# WhiteNoise.net
KiCad netlist of a schematic drawn in EasyEDA
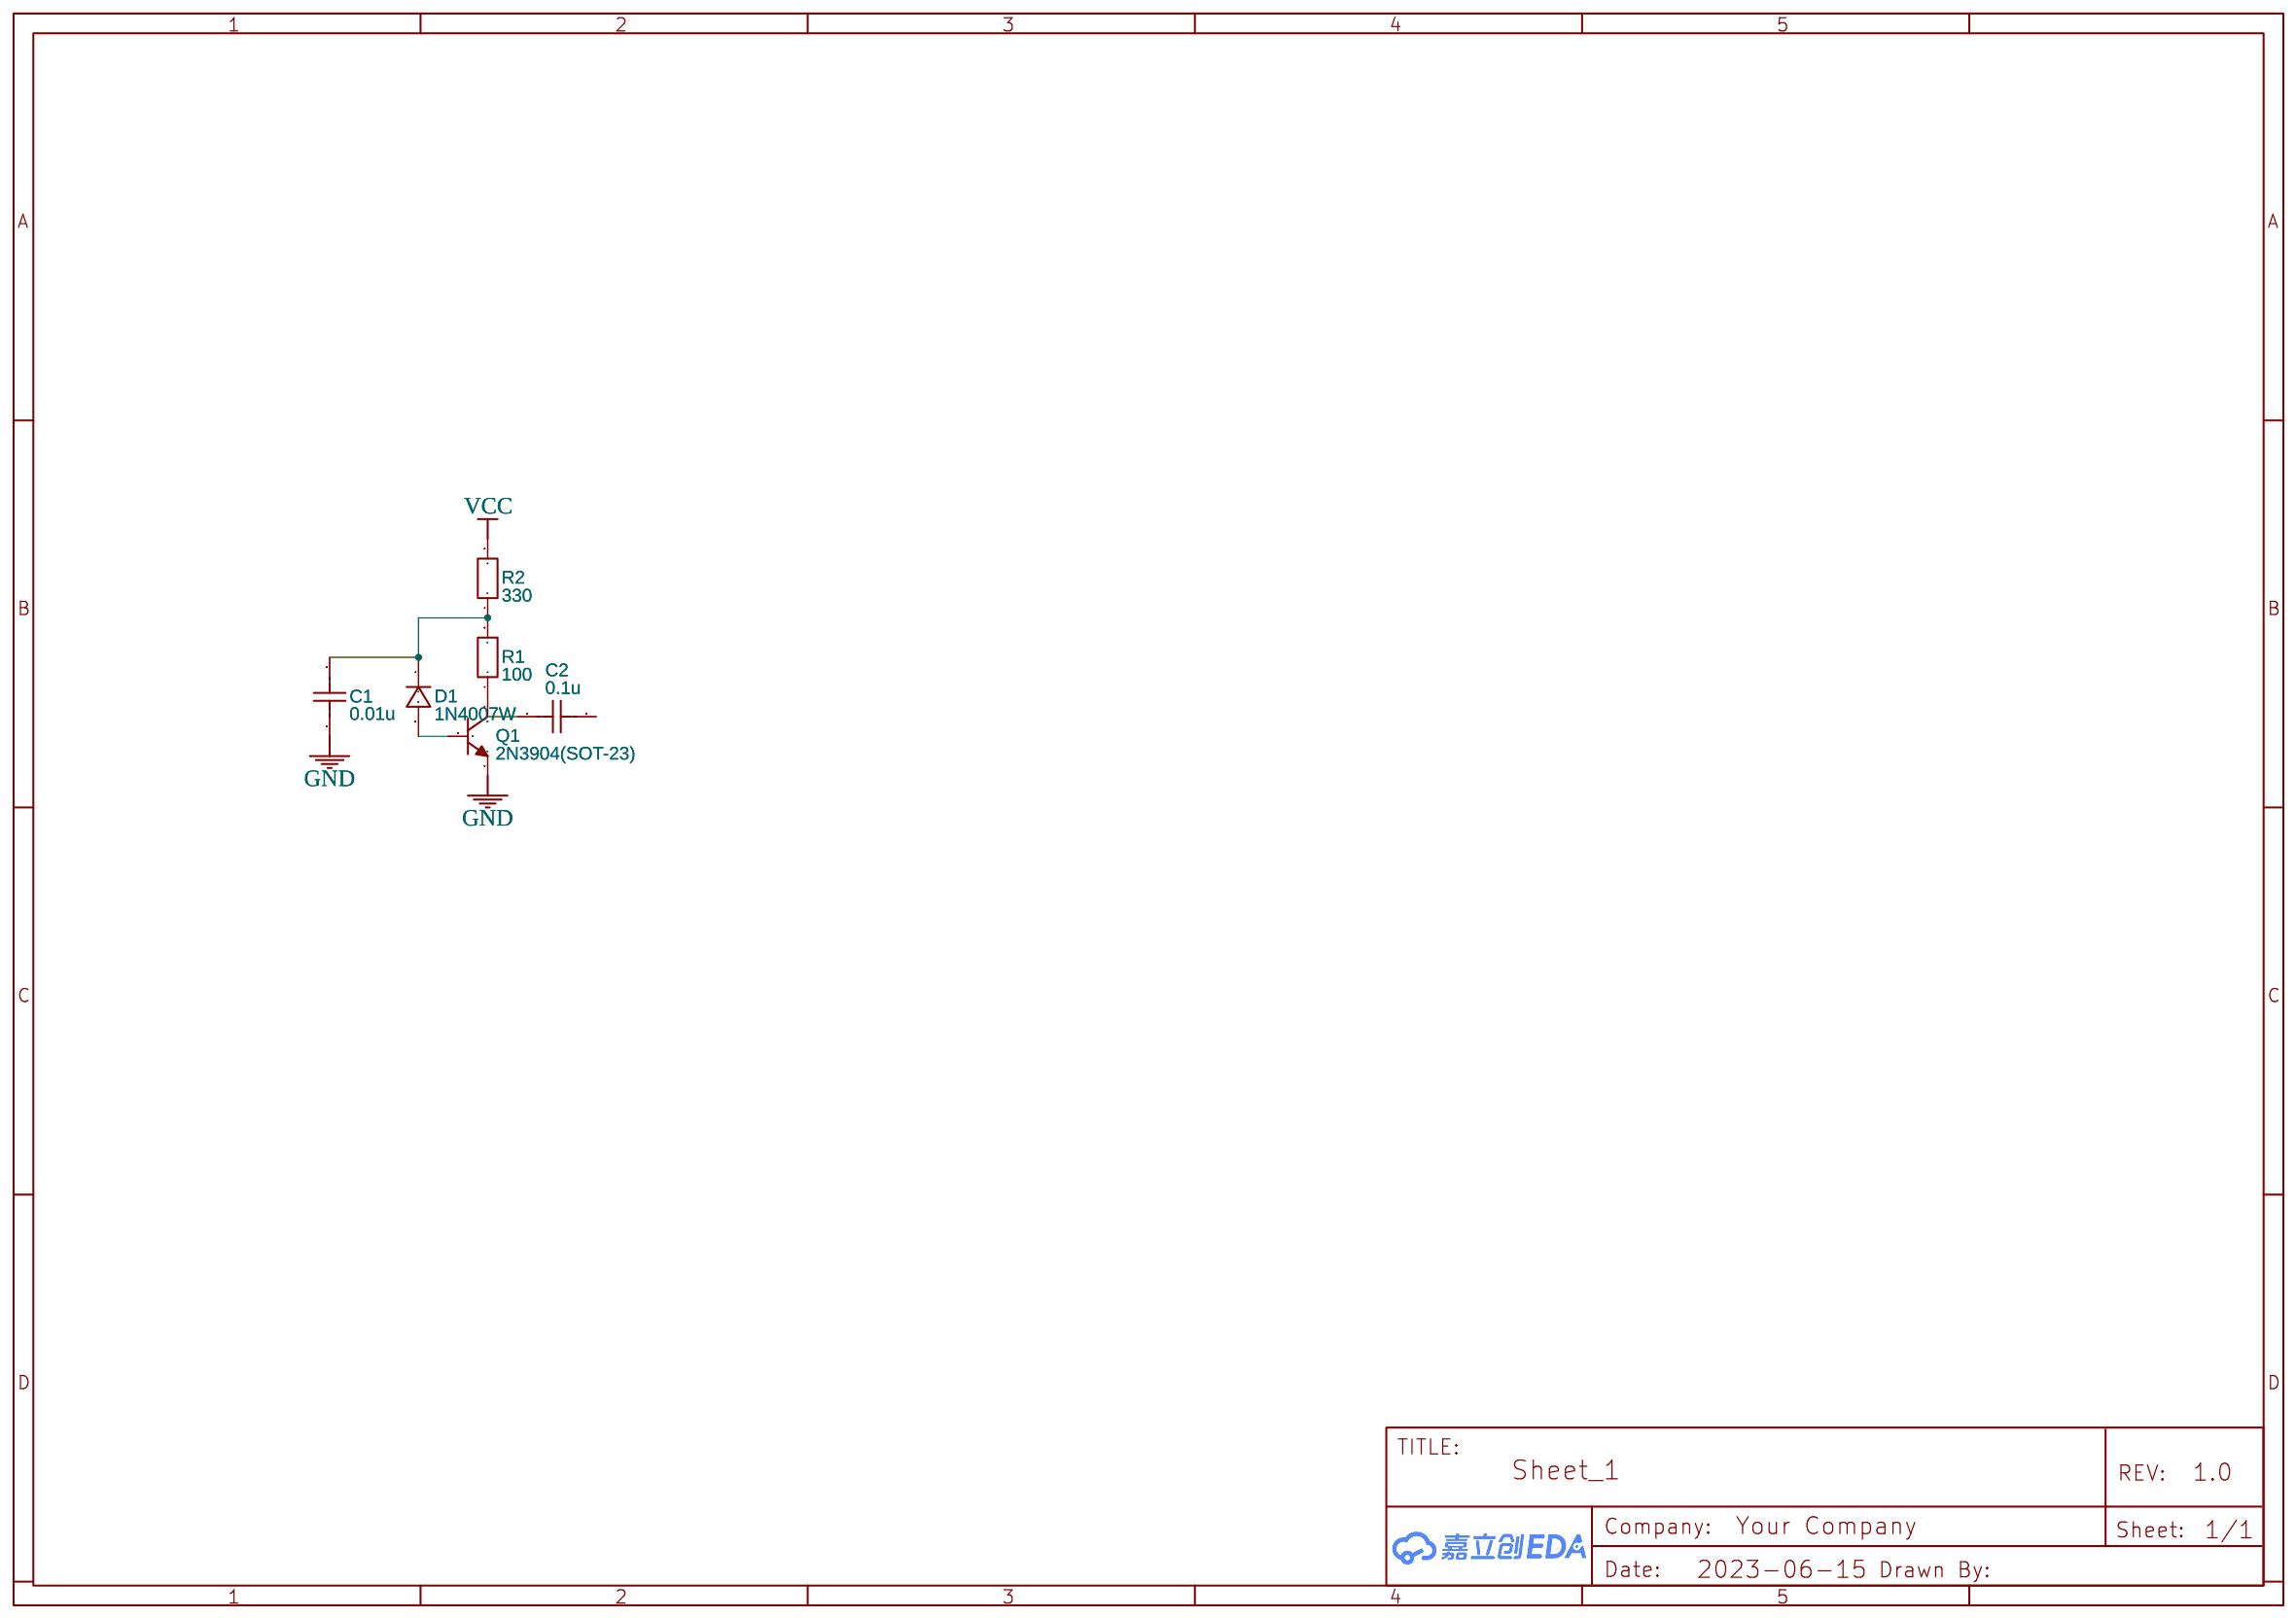
[diagram p0: schematic sheet]

(export (version "E")
  (design (tool "Eeschema 10.0.6"))
  (components
    (comp (ref "C1") (value "0.01u") (libsource (lib "") (part "C_0603_US")))
    (comp (ref "C2") (value "0.1u") (libsource (lib "") (part "C_0603_US_1")))
    (comp (ref "D1")
      (value "1N4007W")
      (fields (field (name "BOM_Supplier Part") "C328592"))
      (libsource (lib "") (part "1N4007W"))
    )
    (comp (ref "Q1")
      (value "2N3904(SOT-23)")
      (fields
        (field (name "BOM_Manufacturer Part") "2n3904S-RTK/PS")
        (field (name "BOM_Supplier Part") "C18536")
      )
      (libsource (lib "") (part "2N3904(SOT-23)"))
    )
    (comp (ref "R1") (value "100") (libsource (lib "") (part "R_0603_EU")))
    (comp (ref "R2") (value "330") (libsource (lib "") (part "R_0603_EU")))
  )
  (nets
    (net (code "1") (name "GND") (class "Default")
      (node (ref "C1") (pin "1") (pinfunction "1_1") (pintype "unspecified"))
      (node (ref "Q1") (pin "2") (pinfunction "E_2") (pintype "input"))
    )
    (net (code "2") (name "Net-(C1-Pad2)") (class "Default")
      (node (ref "C1") (pin "2") (pinfunction "2_2") (pintype "unspecified"))
      (node (ref "D1") (pin "1") (pinfunction "1_1") (pintype "unspecified"))
      (node (ref "R1") (pin "2") (pinfunction "2_2") (pintype "unspecified"))
      (node (ref "R2") (pin "1") (pinfunction "1_1") (pintype "unspecified"))
    )
    (net (code "3") (name "Net-(Q1-B)") (class "Default")
      (node (ref "D1") (pin "2") (pinfunction "2_2") (pintype "unspecified"))
      (node (ref "Q1") (pin "3") (pinfunction "B_3") (pintype "input"))
    )
    (net (code "4") (name "Net-(Q1-C)") (class "Default")
      (node (ref "Q1") (pin "1") (pinfunction "C_1") (pintype "input"))
      (node (ref "R1") (pin "1") (pinfunction "1_1") (pintype "unspecified"))
    )
    (net (code "5") (name "VCC") (class "Default")
      (node (ref "R2") (pin "2") (pinfunction "2_2") (pintype "unspecified"))
    )
    (net (code "6") (name "unconnected-(C2-Pad1)") (class "Default")
      (node (ref "C2") (pin "1") (pinfunction "1_1") (pintype "unspecified"))
    )
    (net (code "7") (name "unconnected-(C2-Pad2)") (class "Default")
      (node (ref "C2") (pin "2") (pinfunction "2_2") (pintype "unspecified"))
    )
  )
)
